# Temperature_Measurement.net
KiCad netlist of a schematic drawn in Altium Designer
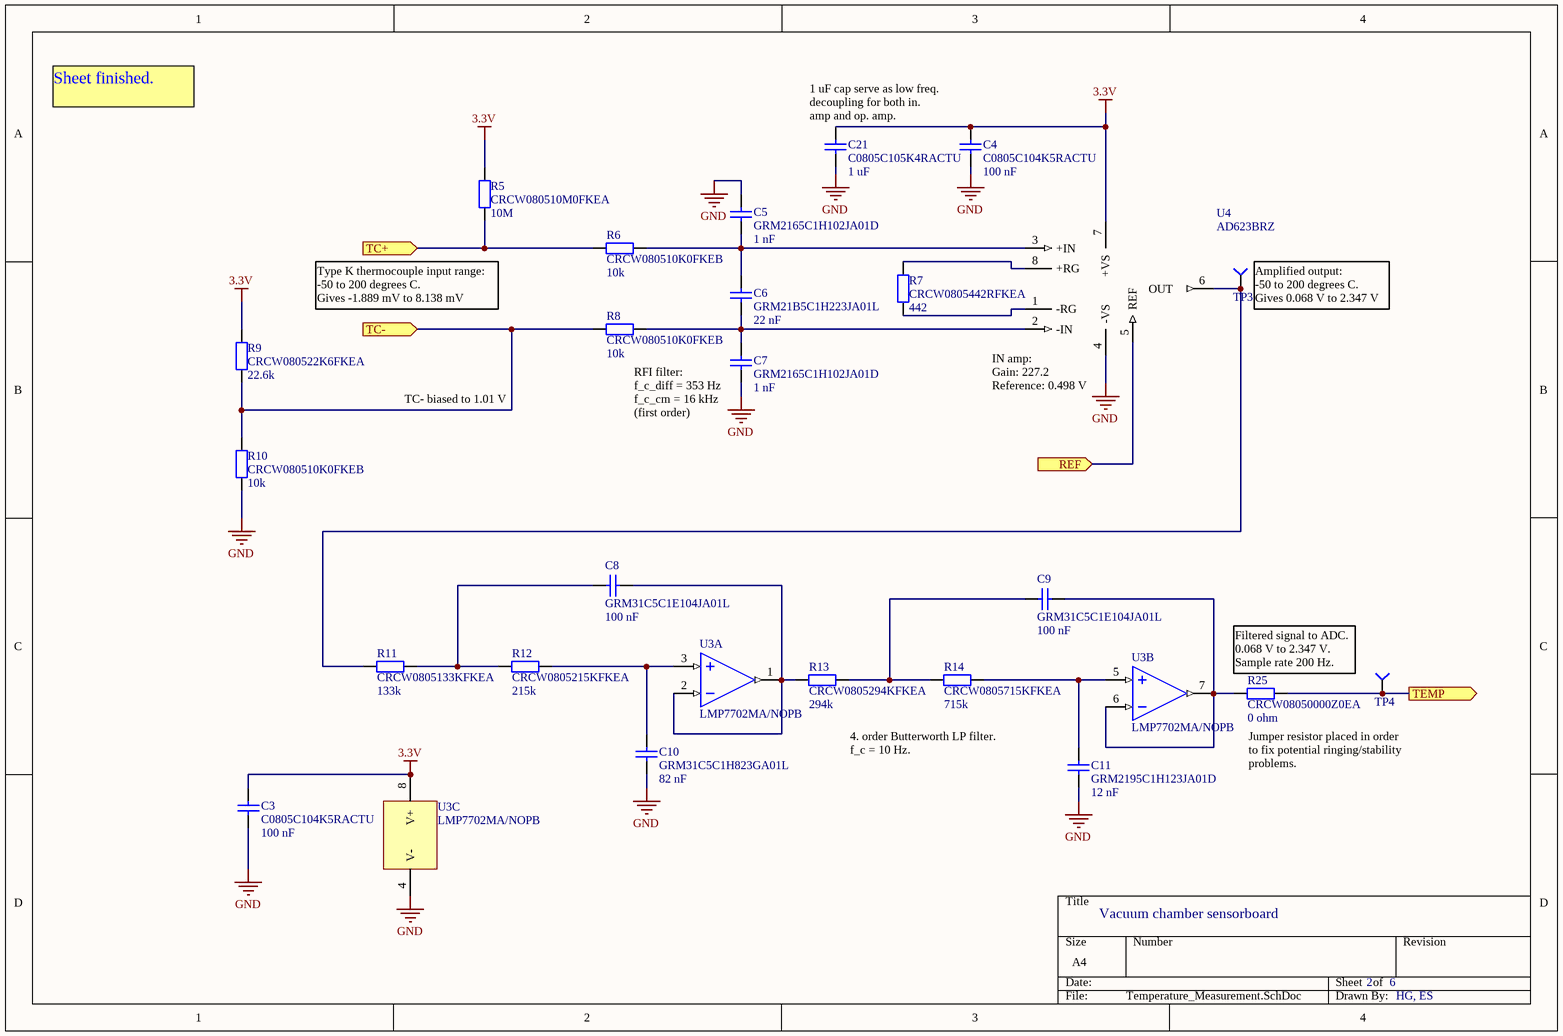
[diagram p0: Temperature_Measurement.SchDoc]

(export (version "E")
  (design (tool "Eeschema 10.0.6"))
  (components
    (comp (ref "C3")
      (value "C0805C104K5RACTU")
      (footprint "Cap Kemet 0805")
      (description "Ceramic capacitor, X7R, 10%, 50V")
      (fields (field (name "MANUFACTURER") "Kemet") (field (name "ALTIUM_VALUE") "100 nF"))
      (libsource (lib "EITlib") (part "C0805C104K5RACTU"))
    )
    (comp (ref "C4")
      (value "C0805C104K5RACTU")
      (footprint "Cap Kemet 0805")
      (description "Ceramic capacitor, X7R, 10%, 50V")
      (fields (field (name "MANUFACTURER") "Kemet") (field (name "ALTIUM_VALUE") "100 nF"))
      (libsource (lib "EITlib") (part "C0805C104K5RACTU"))
    )
    (comp (ref "C5")
      (value "GRM2165C1H102JA01D")
      (footprint "CAP0805 murata")
      (description "Ceramic capacitor, C0G, 5%, 50V")
      (fields (field (name "MANUFACTURER") "Murata") (field (name "ALTIUM_VALUE") "1 nF"))
      (libsource (lib "EITlib") (part "GRM2165C1H102JA01D"))
    )
    (comp (ref "C6")
      (value "GRM21B5C1H223JA01L")
      (footprint "CAP0805 murata")
      (description "Ceramic capacitor, C0G, 5%, 50V")
      (fields (field (name "MANUFACTURER") "Murata") (field (name "ALTIUM_VALUE") "22 nF"))
      (libsource (lib "EITlib") (part "GRM21B5C1H223JA01L"))
    )
    (comp (ref "C7")
      (value "GRM2165C1H102JA01D")
      (footprint "CAP0805 murata")
      (description "Ceramic capacitor, C0G, 5%, 50V")
      (fields (field (name "MANUFACTURER") "Murata") (field (name "ALTIUM_VALUE") "1 nF"))
      (libsource (lib "EITlib") (part "GRM2165C1H102JA01D"))
    )
    (comp (ref "C8")
      (value "GRM31C5C1E104JA01L")
      (footprint "Cap1206 Murata")
      (description "Ceramic capacitor, C0G, 5%, 25V")
      (fields (field (name "MANUFACTURER") "Murata") (field (name "ALTIUM_VALUE") "100 nF"))
      (libsource (lib "EITlib") (part "GRM31C5C1E104JA01L"))
    )
    (comp (ref "C9")
      (value "GRM31C5C1E104JA01L")
      (footprint "Cap1206 Murata")
      (description "Ceramic capacitor, C0G, 5%, 25V")
      (fields (field (name "MANUFACTURER") "Murata") (field (name "ALTIUM_VALUE") "100 nF"))
      (libsource (lib "EITlib") (part "GRM31C5C1E104JA01L"))
    )
    (comp (ref "C10")
      (value "GRM31C5C1H823GA01L")
      (footprint "Cap1206 Murata")
      (description "Ceramic capacitor, C0G, 2%, 50V")
      (fields (field (name "MANUFACTURER") "Murata") (field (name "ALTIUM_VALUE") "82 nF"))
      (libsource (lib "EITlib") (part "GRM31C5C1H823GA01L"))
    )
    (comp (ref "C11")
      (value "GRM2195C1H123JA01D")
      (footprint "CAP0805 murata")
      (description "Ceramic capacitor, C0G, 5%, 50V")
      (fields (field (name "MANUFACTURER") "Murata") (field (name "ALTIUM_VALUE") "12 nF"))
      (libsource (lib "EITlib") (part "GRM2195C1H123JA01D"))
    )
    (comp (ref "C21")
      (value "C0805C105K4RACTU")
      (footprint "Cap Kemet 0805")
      (description "Ceramic capacitor, X7R, 10%, 16V")
      (fields (field (name "MANUFACTURER") "Kemet") (field (name "ALTIUM_VALUE") "1 uF"))
      (libsource (lib "EITlib") (part "C0805C105K4RACTU"))
    )
    (comp (ref "R5")
      (value "CRCW080510M0FKEA")
      (footprint "Res Vishay0805")
      (description "Thick film resistor, 1%, 125mW")
      (fields (field (name "MANUFACTURER") "Vishay") (field (name "ALTIUM_VALUE") "10M"))
      (libsource (lib "EITlib") (part "CRCW080510M0FKEA"))
    )
    (comp (ref "R6")
      (value "CRCW080510K0FKEB")
      (footprint "Res Vishay0805")
      (description "Thick film resistor, 1%, 125mW")
      (fields (field (name "MANUFACTURER") "Vishay") (field (name "ALTIUM_VALUE") "10k"))
      (libsource (lib "EITlib") (part "CRCW080510K0FKEB"))
    )
    (comp (ref "R7")
      (value "CRCW0805442RFKEA")
      (footprint "Res Vishay0805")
      (description "Thick film resistor, 1%, 125mW")
      (fields (field (name "MANUFACTURER") "Vishay") (field (name "ALTIUM_VALUE") "442"))
      (libsource (lib "EITlib") (part "CRCW0805442RFKEA"))
    )
    (comp (ref "R8")
      (value "CRCW080510K0FKEB")
      (footprint "Res Vishay0805")
      (description "Thick film resistor, 1%, 125mW")
      (fields (field (name "MANUFACTURER") "Vishay") (field (name "ALTIUM_VALUE") "10k"))
      (libsource (lib "EITlib") (part "CRCW080510K0FKEB"))
    )
    (comp (ref "R9")
      (value "CRCW080522K6FKEA")
      (footprint "Res Vishay0805")
      (description "Thick film resistor, 1%, 125mW")
      (fields (field (name "MANUFACTURER") "Vishay") (field (name "ALTIUM_VALUE") "22.6k"))
      (libsource (lib "EITlib") (part "CRCW080522K6FKEA"))
    )
    (comp (ref "R10")
      (value "CRCW080510K0FKEB")
      (footprint "Res Vishay0805")
      (description "Thick film resistor, 1%, 125mW")
      (fields (field (name "MANUFACTURER") "Vishay") (field (name "ALTIUM_VALUE") "10k"))
      (libsource (lib "") (part "CRCW080510K0FKEB_1"))
    )
    (comp (ref "R11")
      (value "CRCW0805133KFKEA")
      (footprint "Res Vishay0805")
      (description "Thick film resistor, 1%, 125mW")
      (fields (field (name "MANUFACTURER") "Vishay") (field (name "ALTIUM_VALUE") "133k"))
      (libsource (lib "EITlib") (part "CRCW0805133KFKEA"))
    )
    (comp (ref "R12")
      (value "CRCW0805215KFKEA")
      (footprint "Res Vishay0805")
      (description "Thick film resistor, 1%, 125mW")
      (fields (field (name "MANUFACTURER") "Vishay") (field (name "ALTIUM_VALUE") "215k"))
      (libsource (lib "EITlib") (part "CRCW0805215KFKEA"))
    )
    (comp (ref "R13")
      (value "CRCW0805294KFKEA")
      (footprint "Res Vishay0805")
      (description "Thick film resistor, 1%, 125mW")
      (fields (field (name "MANUFACTURER") "Vishay") (field (name "ALTIUM_VALUE") "294k"))
      (libsource (lib "EITlib") (part "CRCW0805294KFKEA"))
    )
    (comp (ref "R14")
      (value "CRCW0805715KFKEA")
      (footprint "Res Vishay0805")
      (description "Thick film resistor, 1%, 125mW")
      (fields (field (name "MANUFACTURER") "Vishay") (field (name "ALTIUM_VALUE") "715k"))
      (libsource (lib "EITlib") (part "CRCW0805715KFKEA"))
    )
    (comp (ref "R25")
      (value "CRCW08050000Z0EA")
      (footprint "Res Vishay0805")
      (description "Thick film resistor, 1%, 125mW")
      (fields (field (name "MANUFACTURER") "Vishay") (field (name "ALTIUM_VALUE") "0 ohm"))
      (libsource (lib "EITlib") (part "CRCW08050000Z0EA"))
    )
    (comp (ref "TP3")
      (value "Test_point")
      (footprint "Testpoint")
      (libsource (lib "EITlib") (part "Test_point"))
    )
    (comp (ref "TP4")
      (value "Test_point")
      (footprint "Testpoint")
      (libsource (lib "EITlib") (part "Test_point"))
    )
    (comp (ref "U3")
      (value "LMP7702MA/NOPB")
      (footprint "OPA2333AIDR")
      (description "Op. amp, dual, rail-to-rail, single supply")
      (libsource (lib "") (part "LMP7702MA/NOPB_1"))
    )
    (comp (ref "U4")
      (value "AD623BRZ")
      (footprint "AD623")
      (description "Instrumentation amplifier, rail to rail")
      (libsource (lib "EITlib") (part "AD623BRZ"))
    )
  )
  (nets
    (net (code "1") (name "/REF") (class "Default")
      (node (ref "U4") (pin "5") (pinfunction "REF_5") (pintype "input"))
    )
    (net (code "2") (name "/TC+") (class "Default")
      (node (ref "R5") (pin "1") (pinfunction "1_1") (pintype "passive"))
      (node (ref "R6") (pin "1") (pinfunction "1_1") (pintype "passive"))
    )
    (net (code "3") (name "/TC-") (class "Default")
      (node (ref "R10") (pin "2") (pinfunction "2_2") (pintype "passive"))
      (node (ref "R8") (pin "1") (pinfunction "1_1") (pintype "passive"))
      (node (ref "R9") (pin "1") (pinfunction "1_1") (pintype "passive"))
    )
    (net (code "4") (name "/TEMP") (class "Default")
      (node (ref "R25") (pin "2") (pinfunction "2_2") (pintype "passive"))
      (node (ref "TP4") (pin "0") (pinfunction "0_0") (pintype "passive"))
    )
    (net (code "5") (name "3.3V") (class "Default")
      (node (ref "C21") (pin "2") (pinfunction "2_2") (pintype "passive"))
      (node (ref "C3") (pin "2") (pinfunction "2_2") (pintype "passive"))
      (node (ref "C4") (pin "2") (pinfunction "2_2") (pintype "passive"))
      (node (ref "R5") (pin "2") (pinfunction "2_2") (pintype "passive"))
      (node (ref "R9") (pin "2") (pinfunction "2_2") (pintype "passive"))
      (node (ref "U3") (pin "8") (pinfunction "V+_8") (pintype "power_in"))
      (node (ref "U4") (pin "7") (pinfunction "+VS_7") (pintype "power_in"))
    )
    (net (code "6") (name "GND") (class "Default")
      (node (ref "C10") (pin "1") (pinfunction "1_1") (pintype "passive"))
      (node (ref "C11") (pin "1") (pinfunction "1_1") (pintype "passive"))
      (node (ref "C21") (pin "1") (pinfunction "1_1") (pintype "passive"))
      (node (ref "C3") (pin "1") (pinfunction "1_1") (pintype "passive"))
      (node (ref "C4") (pin "1") (pinfunction "1_1") (pintype "passive"))
      (node (ref "C5") (pin "2") (pinfunction "2_2") (pintype "passive"))
      (node (ref "C7") (pin "1") (pinfunction "1_1") (pintype "passive"))
      (node (ref "R10") (pin "1") (pinfunction "1_1") (pintype "passive"))
      (node (ref "U3") (pin "4") (pinfunction "V-_4") (pintype "power_in"))
      (node (ref "U4") (pin "4") (pinfunction "-VS_4") (pintype "power_in"))
    )
    (net (code "7") (name "Net-(C8-Pad2)") (class "Default")
      (node (ref "C8") (pin "2") (pinfunction "2_2") (pintype "passive"))
      (node (ref "R11") (pin "2") (pinfunction "2_2") (pintype "passive"))
      (node (ref "R12") (pin "1") (pinfunction "1_1") (pintype "passive"))
    )
    (net (code "8") (name "Net-(C9-Pad2)") (class "Default")
      (node (ref "C9") (pin "2") (pinfunction "2_2") (pintype "passive"))
      (node (ref "R13") (pin "2") (pinfunction "2_2") (pintype "passive"))
      (node (ref "R14") (pin "1") (pinfunction "1_1") (pintype "passive"))
    )
    (net (code "9") (name "Net-(U3A-+IN_A)") (class "Default")
      (node (ref "C10") (pin "2") (pinfunction "2_2") (pintype "passive"))
      (node (ref "R12") (pin "2") (pinfunction "2_2") (pintype "passive"))
      (node (ref "U3") (pin "3") (pinfunction "+IN_A_3") (pintype "input"))
    )
    (net (code "10") (name "Net-(U3A--IN_A)") (class "Default")
      (node (ref "C8") (pin "1") (pinfunction "1_1") (pintype "passive"))
      (node (ref "R13") (pin "1") (pinfunction "1_1") (pintype "passive"))
      (node (ref "U3") (pin "1") (pinfunction "OUT_A_1") (pintype "output"))
      (node (ref "U3") (pin "2") (pinfunction "-IN_A_2") (pintype "input"))
    )
    (net (code "11") (name "Net-(U3B-+IN_B)") (class "Default")
      (node (ref "C11") (pin "2") (pinfunction "2_2") (pintype "passive"))
      (node (ref "R14") (pin "2") (pinfunction "2_2") (pintype "passive"))
      (node (ref "U3") (pin "5") (pinfunction "+IN_B_5") (pintype "input"))
    )
    (net (code "12") (name "Net-(U3B--IN_B)") (class "Default")
      (node (ref "C9") (pin "1") (pinfunction "1_1") (pintype "passive"))
      (node (ref "R25") (pin "1") (pinfunction "1_1") (pintype "passive"))
      (node (ref "U3") (pin "6") (pinfunction "-IN_B_6") (pintype "input"))
      (node (ref "U3") (pin "7") (pinfunction "OUT_B_7") (pintype "output"))
    )
    (net (code "13") (name "Net-(U4-+IN)") (class "Default")
      (node (ref "C5") (pin "1") (pinfunction "1_1") (pintype "passive"))
      (node (ref "C6") (pin "2") (pinfunction "2_2") (pintype "passive"))
      (node (ref "R6") (pin "2") (pinfunction "2_2") (pintype "passive"))
      (node (ref "U4") (pin "3") (pinfunction "+IN_3") (pintype "input"))
    )
    (net (code "14") (name "Net-(U4-+RG)") (class "Default")
      (node (ref "R7") (pin "2") (pinfunction "2_2") (pintype "passive"))
      (node (ref "U4") (pin "8") (pinfunction "+RG_8") (pintype "passive"))
    )
    (net (code "15") (name "Net-(U4--IN)") (class "Default")
      (node (ref "C6") (pin "1") (pinfunction "1_1") (pintype "passive"))
      (node (ref "C7") (pin "2") (pinfunction "2_2") (pintype "passive"))
      (node (ref "R8") (pin "2") (pinfunction "2_2") (pintype "passive"))
      (node (ref "U4") (pin "2") (pinfunction "-IN_2") (pintype "input"))
    )
    (net (code "16") (name "Net-(U4--RG)") (class "Default")
      (node (ref "R7") (pin "1") (pinfunction "1_1") (pintype "passive"))
      (node (ref "U4") (pin "1") (pinfunction "-RG_1") (pintype "passive"))
    )
    (net (code "17") (name "Net-(U4-OUT)") (class "Default")
      (node (ref "R11") (pin "1") (pinfunction "1_1") (pintype "passive"))
      (node (ref "TP3") (pin "0") (pinfunction "0_0") (pintype "passive"))
      (node (ref "U4") (pin "6") (pinfunction "OUT_6") (pintype "output"))
    )
  )
)
